# led.net
KiCad netlist of a schematic drawn in Altium Designer
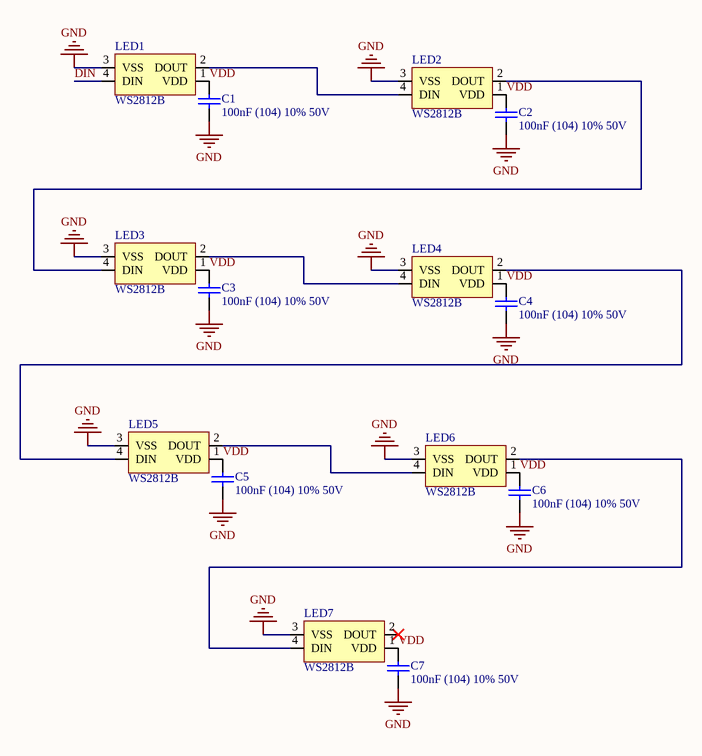
[diagram p0: led.SchDoc]

(export (version "E")
  (design (tool "Eeschema 10.0.6"))
  (components
    (comp (ref "C1")
      (value "100nF (104) 10% 50V")
      (footprint "0603_C")
      (description "贴片电容")
      (libsource (lib "Miscellaneous Devices LC") (part "0603 100nF (104) 10% 50V"))
    )
    (comp (ref "C2")
      (value "100nF (104) 10% 50V")
      (footprint "0603_C")
      (description "贴片电容")
      (libsource (lib "Miscellaneous Devices LC") (part "0603 100nF (104) 10% 50V"))
    )
    (comp (ref "C3")
      (value "100nF (104) 10% 50V")
      (footprint "0603_C")
      (description "贴片电容")
      (libsource (lib "Miscellaneous Devices LC") (part "0603 100nF (104) 10% 50V"))
    )
    (comp (ref "C4")
      (value "100nF (104) 10% 50V")
      (footprint "0603_C")
      (description "贴片电容")
      (libsource (lib "Miscellaneous Devices LC") (part "0603 100nF (104) 10% 50V"))
    )
    (comp (ref "C5")
      (value "100nF (104) 10% 50V")
      (footprint "0603_C")
      (description "贴片电容")
      (libsource (lib "Miscellaneous Devices LC") (part "0603 100nF (104) 10% 50V"))
    )
    (comp (ref "C6")
      (value "100nF (104) 10% 50V")
      (footprint "0603_C")
      (description "贴片电容")
      (libsource (lib "Miscellaneous Devices LC") (part "0603 100nF (104) 10% 50V"))
    )
    (comp (ref "C7")
      (value "100nF (104) 10% 50V")
      (footprint "0603_C")
      (description "贴片电容")
      (libsource (lib "Miscellaneous Devices LC") (part "0603 100nF (104) 10% 50V"))
    )
    (comp (ref "LED1") (value "WS2812B") (footprint "WS2812") (libsource (lib "mylib") (part "WS2812B")))
    (comp (ref "LED2") (value "WS2812B") (footprint "WS2812") (libsource (lib "mylib") (part "WS2812B")))
    (comp (ref "LED3") (value "WS2812B") (footprint "WS2812") (libsource (lib "mylib") (part "WS2812B")))
    (comp (ref "LED4") (value "WS2812B") (footprint "WS2812") (libsource (lib "mylib") (part "WS2812B")))
    (comp (ref "LED5") (value "WS2812B") (footprint "WS2812") (libsource (lib "mylib") (part "WS2812B")))
    (comp (ref "LED6") (value "WS2812B") (footprint "WS2812") (libsource (lib "mylib") (part "WS2812B")))
    (comp (ref "LED7") (value "WS2812B") (footprint "WS2812") (libsource (lib "mylib") (part "WS2812B")))
  )
  (nets
    (net (code "1") (name "/DIN") (class "Default")
      (node (ref "LED1") (pin "4") (pinfunction "DIN_4") (pintype "passive"))
    )
    (net (code "2") (name "/VDD") (class "Default")
      (node (ref "C1") (pin "1") (pinfunction "1_1") (pintype "passive"))
      (node (ref "C2") (pin "1") (pinfunction "1_1") (pintype "passive"))
      (node (ref "C3") (pin "1") (pinfunction "1_1") (pintype "passive"))
      (node (ref "C4") (pin "1") (pinfunction "1_1") (pintype "passive"))
      (node (ref "C5") (pin "1") (pinfunction "1_1") (pintype "passive"))
      (node (ref "C6") (pin "1") (pinfunction "1_1") (pintype "passive"))
      (node (ref "C7") (pin "1") (pinfunction "1_1") (pintype "passive"))
      (node (ref "LED1") (pin "1") (pinfunction "VDD_1") (pintype "passive"))
      (node (ref "LED2") (pin "1") (pinfunction "VDD_1") (pintype "passive"))
      (node (ref "LED3") (pin "1") (pinfunction "VDD_1") (pintype "passive"))
      (node (ref "LED4") (pin "1") (pinfunction "VDD_1") (pintype "passive"))
      (node (ref "LED5") (pin "1") (pinfunction "VDD_1") (pintype "passive"))
      (node (ref "LED6") (pin "1") (pinfunction "VDD_1") (pintype "passive"))
      (node (ref "LED7") (pin "1") (pinfunction "VDD_1") (pintype "passive"))
    )
    (net (code "3") (name "GND") (class "Default")
      (node (ref "C1") (pin "2") (pinfunction "2_2") (pintype "passive"))
      (node (ref "C2") (pin "2") (pinfunction "2_2") (pintype "passive"))
      (node (ref "C3") (pin "2") (pinfunction "2_2") (pintype "passive"))
      (node (ref "C4") (pin "2") (pinfunction "2_2") (pintype "passive"))
      (node (ref "C5") (pin "2") (pinfunction "2_2") (pintype "passive"))
      (node (ref "C6") (pin "2") (pinfunction "2_2") (pintype "passive"))
      (node (ref "C7") (pin "2") (pinfunction "2_2") (pintype "passive"))
      (node (ref "LED1") (pin "3") (pinfunction "VSS_3") (pintype "passive"))
      (node (ref "LED2") (pin "3") (pinfunction "VSS_3") (pintype "passive"))
      (node (ref "LED3") (pin "3") (pinfunction "VSS_3") (pintype "passive"))
      (node (ref "LED4") (pin "3") (pinfunction "VSS_3") (pintype "passive"))
      (node (ref "LED5") (pin "3") (pinfunction "VSS_3") (pintype "passive"))
      (node (ref "LED6") (pin "3") (pinfunction "VSS_3") (pintype "passive"))
      (node (ref "LED7") (pin "3") (pinfunction "VSS_3") (pintype "passive"))
    )
    (net (code "4") (name "Net-(LED1-DOUT)") (class "Default")
      (node (ref "LED1") (pin "2") (pinfunction "DOUT_2") (pintype "passive"))
      (node (ref "LED2") (pin "4") (pinfunction "DIN_4") (pintype "passive"))
    )
    (net (code "5") (name "Net-(LED2-DOUT)") (class "Default")
      (node (ref "LED2") (pin "2") (pinfunction "DOUT_2") (pintype "passive"))
      (node (ref "LED3") (pin "4") (pinfunction "DIN_4") (pintype "passive"))
    )
    (net (code "6") (name "Net-(LED3-DOUT)") (class "Default")
      (node (ref "LED3") (pin "2") (pinfunction "DOUT_2") (pintype "passive"))
      (node (ref "LED4") (pin "4") (pinfunction "DIN_4") (pintype "passive"))
    )
    (net (code "7") (name "Net-(LED4-DOUT)") (class "Default")
      (node (ref "LED4") (pin "2") (pinfunction "DOUT_2") (pintype "passive"))
      (node (ref "LED5") (pin "4") (pinfunction "DIN_4") (pintype "passive"))
    )
    (net (code "8") (name "Net-(LED5-DOUT)") (class "Default")
      (node (ref "LED5") (pin "2") (pinfunction "DOUT_2") (pintype "passive"))
      (node (ref "LED6") (pin "4") (pinfunction "DIN_4") (pintype "passive"))
    )
    (net (code "9") (name "Net-(LED6-DOUT)") (class "Default")
      (node (ref "LED6") (pin "2") (pinfunction "DOUT_2") (pintype "passive"))
      (node (ref "LED7") (pin "4") (pinfunction "DIN_4") (pintype "passive"))
    )
    (net (code "10") (name "unconnected-(LED7-DOUT-Pad2)") (class "Default")
      (node (ref "LED7") (pin "2") (pinfunction "DOUT_2") (pintype "passive+no_connect"))
    )
  )
)
